# MD_Switchless.net
KiCad netlist of a schematic drawn in EAGLE
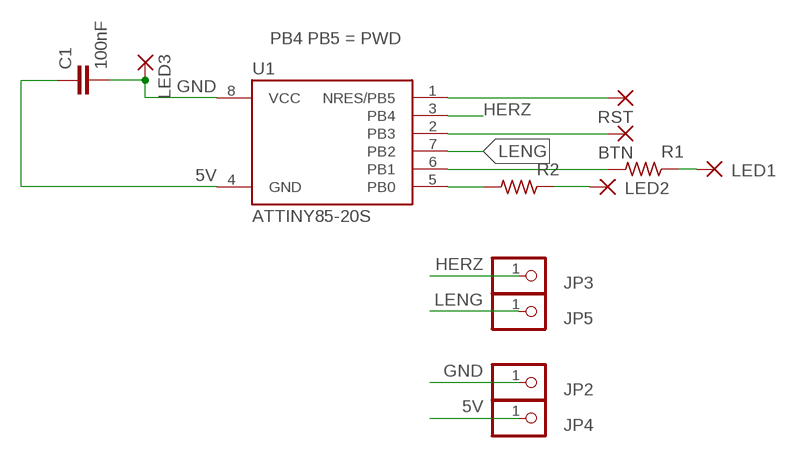
[diagram p0: schematic, sheet 1]

(export (version "E")
  (design (tool "Eeschema 10.0.6"))
  (components
    (comp (ref "BTN")
      (value "WIREPADSMD1,27-254")
      (footprint "eagle-import:SMD1,27-2,54")
      (libsource (lib "eagle-import") (part "WIREPADSMD1,27-254"))
    )
    (comp (ref "C1")
      (value "100nF")
      (footprint "eagle-import:0805")
      (libsource (lib "eagle-import") (part "1.0UF-0805-25V-10%"))
    )
    (comp (ref "JP2")
      (value "PINHD-1X1")
      (footprint "eagle-import:1X01")
      (libsource (lib "eagle-import") (part "PINHD-1X1"))
    )
    (comp (ref "JP3")
      (value "PINHD-1X1")
      (footprint "eagle-import:1X01")
      (libsource (lib "eagle-import") (part "PINHD-1X1"))
    )
    (comp (ref "JP4")
      (value "PINHD-1X1")
      (footprint "eagle-import:1X01")
      (libsource (lib "eagle-import") (part "PINHD-1X1"))
    )
    (comp (ref "JP5")
      (value "PINHD-1X1")
      (footprint "eagle-import:1X01")
      (libsource (lib "eagle-import") (part "PINHD-1X1"))
    )
    (comp (ref "LED1")
      (value "WIREPADSMD1,27-254")
      (footprint "eagle-import:SMD1,27-2,54")
      (libsource (lib "eagle-import") (part "WIREPADSMD1,27-254"))
    )
    (comp (ref "LED2")
      (value "WIREPADSMD1,27-254")
      (footprint "eagle-import:SMD1,27-2,54")
      (libsource (lib "eagle-import") (part "WIREPADSMD1,27-254"))
    )
    (comp (ref "LED3")
      (value "WIREPADSMD1,27-254")
      (footprint "eagle-import:SMD1,27-2,54")
      (libsource (lib "eagle-import") (part "WIREPADSMD1,27-254"))
    )
    (comp (ref "R1")
      (value "R_0805")
      (footprint "eagle-import:R0805")
      (libsource (lib "eagle-import") (part "R_0805"))
    )
    (comp (ref "R2")
      (value "R_0805")
      (footprint "eagle-import:R0805")
      (libsource (lib "eagle-import") (part "R_0805"))
    )
    (comp (ref "RST")
      (value "WIREPADSMD1,27-254")
      (footprint "eagle-import:SMD1,27-2,54")
      (libsource (lib "eagle-import") (part "WIREPADSMD1,27-254"))
    )
    (comp (ref "U1")
      (value "ATTINY85-20S")
      (footprint "eagle-import:SOIC8_EIAJ_208MIL")
      (libsource (lib "eagle-import") (part "ATTINY85S-20"))
    )
  )
  (nets
    (net (code "1") (name "/5V") (class "Default")
      (node (ref "C1") (pin "1") (pinfunction "1_1") (pintype "passive"))
      (node (ref "JP4") (pin "1") (pinfunction "1_1") (pintype "passive"))
      (node (ref "U1") (pin "4") (pinfunction "GND_4") (pintype "power_in"))
    )
    (net (code "2") (name "/GND") (class "Default")
      (node (ref "C1") (pin "2") (pinfunction "2_2") (pintype "passive"))
      (node (ref "JP2") (pin "1") (pinfunction "1_1") (pintype "passive"))
      (node (ref "LED3") (pin "1") (pinfunction "P_1") (pintype "passive"))
      (node (ref "U1") (pin "8") (pinfunction "VCC_8") (pintype "power_in"))
    )
    (net (code "3") (name "/HERZ") (class "Default")
      (node (ref "JP3") (pin "1") (pinfunction "1_1") (pintype "passive"))
      (node (ref "U1") (pin "3") (pinfunction "PB4_3") (pintype "bidirectional"))
    )
    (net (code "4") (name "LENG") (class "Default")
      (node (ref "JP5") (pin "1") (pinfunction "1_1") (pintype "passive"))
      (node (ref "U1") (pin "7") (pinfunction "PB2_7") (pintype "bidirectional"))
    )
    (net (code "5") (name "Net-(BTN-P)") (class "Default")
      (node (ref "BTN") (pin "1") (pinfunction "P_1") (pintype "passive"))
      (node (ref "U1") (pin "2") (pinfunction "PB3_2") (pintype "bidirectional"))
    )
    (net (code "6") (name "Net-(LED1-P)") (class "Default")
      (node (ref "LED1") (pin "1") (pinfunction "P_1") (pintype "passive"))
      (node (ref "R1") (pin "2") (pinfunction "2_2") (pintype "passive"))
    )
    (net (code "7") (name "Net-(LED2-P)") (class "Default")
      (node (ref "LED2") (pin "1") (pinfunction "P_1") (pintype "passive"))
      (node (ref "R2") (pin "2") (pinfunction "2_2") (pintype "passive"))
    )
    (net (code "8") (name "Net-(RST-P)") (class "Default")
      (node (ref "RST") (pin "1") (pinfunction "P_1") (pintype "passive"))
      (node (ref "U1") (pin "1") (pinfunction "NRES/PB5_1") (pintype "bidirectional"))
    )
    (net (code "9") (name "Net-(U1-PB0)") (class "Default")
      (node (ref "R2") (pin "1") (pinfunction "1_1") (pintype "passive"))
      (node (ref "U1") (pin "5") (pinfunction "PB0_5") (pintype "bidirectional"))
    )
    (net (code "10") (name "Net-(U1-PB1)") (class "Default")
      (node (ref "R1") (pin "1") (pinfunction "1_1") (pintype "passive"))
      (node (ref "U1") (pin "6") (pinfunction "PB1_6") (pintype "bidirectional"))
    )
  )
)
